# Arduino-DIP.net
KiCad netlist of a schematic drawn in EAGLE
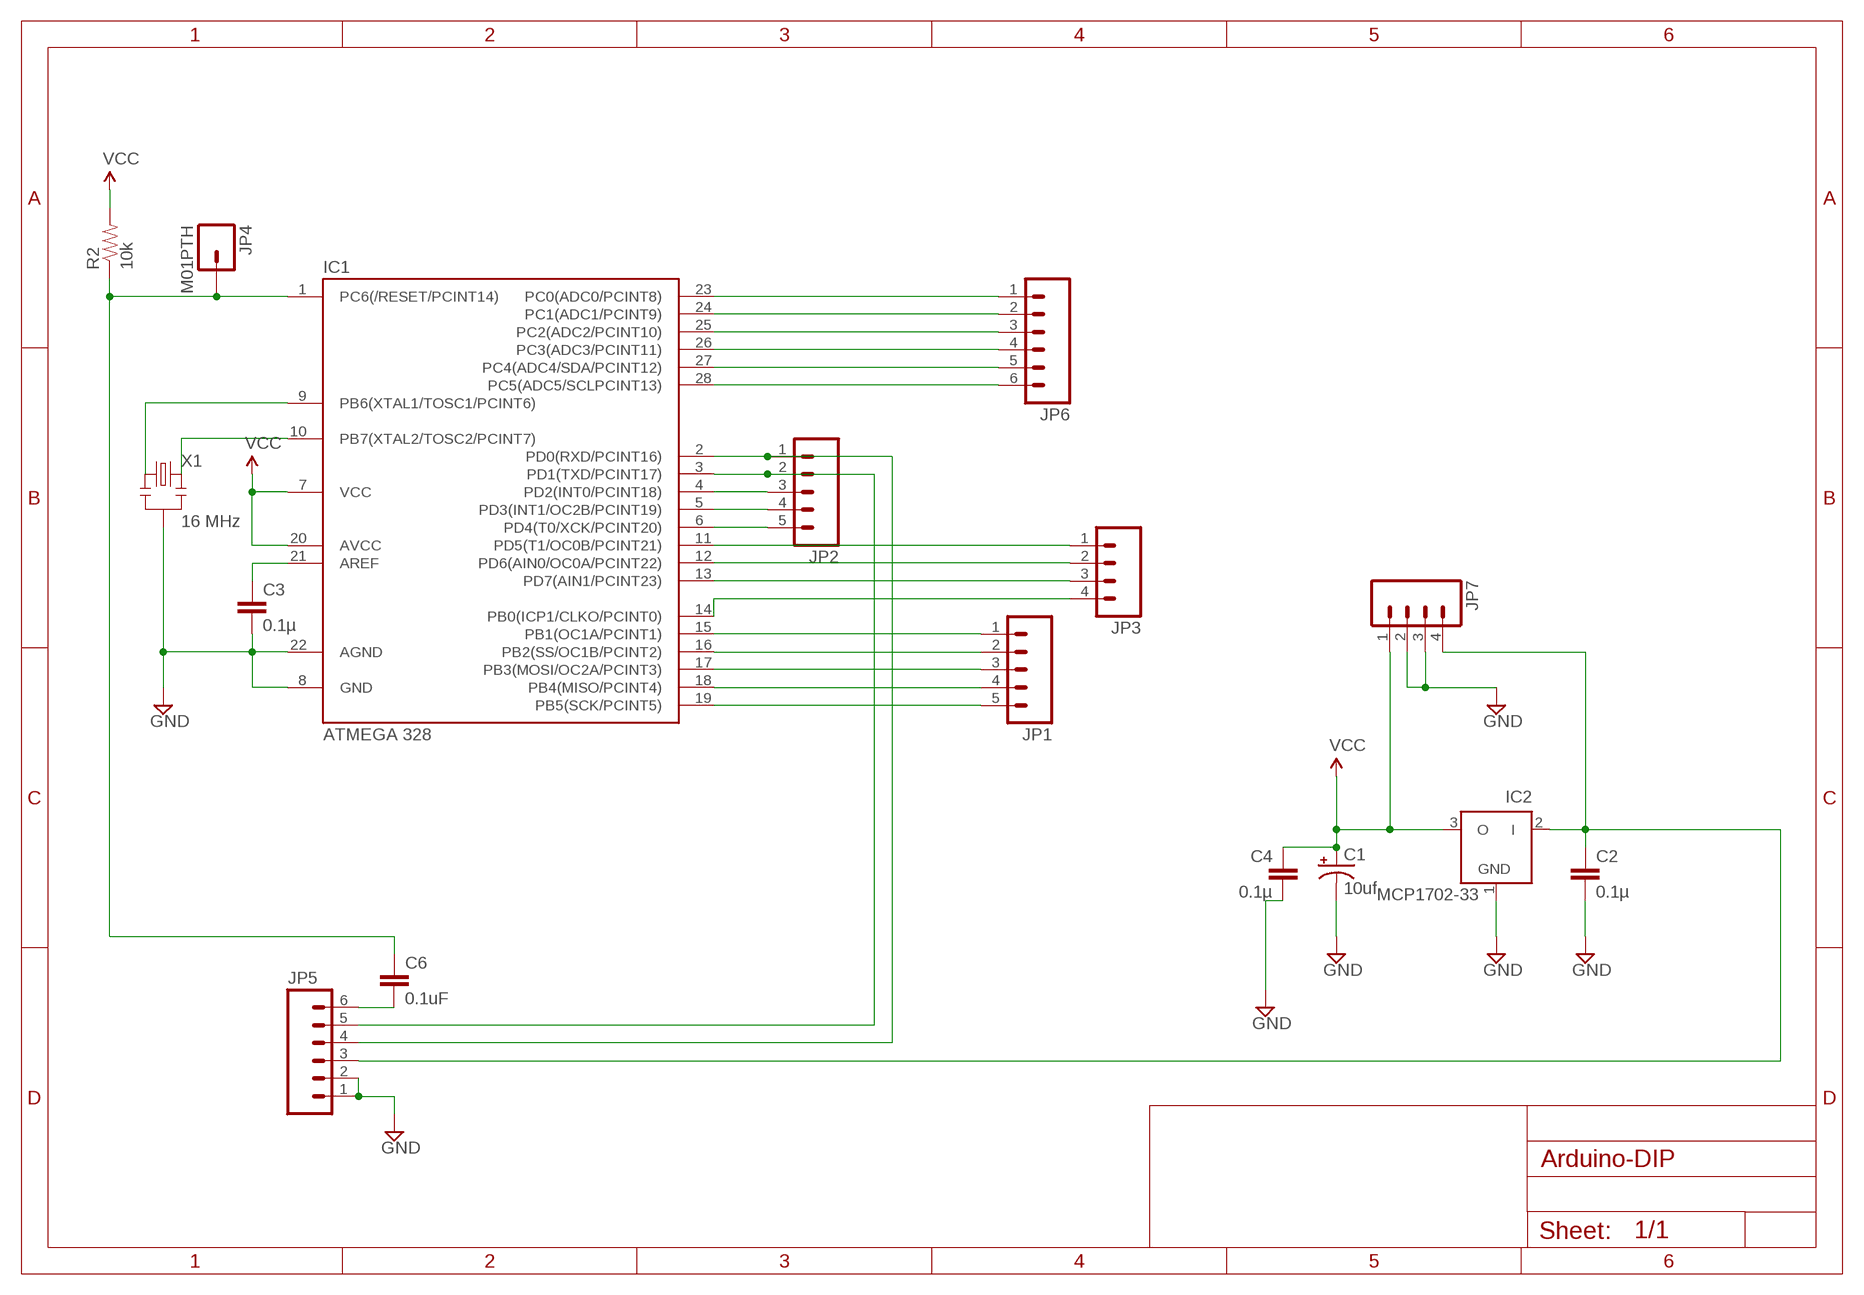
[diagram p0: schematic, sheet 1]

(export (version "E")
  (design (tool "Eeschema 10.0.6"))
  (components
    (comp (ref "C1")
      (value "10uf")
      (footprint "eagle-import:CPOL-RADIAL-10UF-25V")
      (libsource (lib "eagle-import") (part "CAP_POLPTH2"))
    )
    (comp (ref "C2")
      (value "0.1µ")
      (footprint "eagle-import:C025-024X044")
      (libsource (lib "eagle-import") (part "C-EU025-024X044"))
    )
    (comp (ref "C3")
      (value "0.1µ")
      (footprint "eagle-import:C025-024X044")
      (libsource (lib "eagle-import") (part "C-EU025-024X044"))
    )
    (comp (ref "C4")
      (value "0.1µ")
      (footprint "eagle-import:C025-024X044")
      (libsource (lib "eagle-import") (part "C-EU025-024X044"))
    )
    (comp (ref "C6")
      (value "0.1uF")
      (footprint "eagle-import:CAP-PTH-5MM")
      (libsource (lib "eagle-import") (part "CAPPTH1"))
    )
    (comp (ref "IC1")
      (value "ATMEGA 328")
      (footprint "eagle-import:DIL28-3")
      (libsource (lib "eagle-import") (part "ATMEGA48/88/168-PU"))
    )
    (comp (ref "IC2")
      (value "MCP1702-33")
      (footprint "eagle-import:TO92")
      (libsource (lib "eagle-import") (part "MCP1702Z"))
    )
    (comp (ref "JP1")
      (value "M05PTH")
      (footprint "eagle-import:1X05")
      (libsource (lib "eagle-import") (part "M05PTH"))
    )
    (comp (ref "JP2")
      (value "M05PTH")
      (footprint "eagle-import:1X05")
      (libsource (lib "eagle-import") (part "M05PTH"))
    )
    (comp (ref "JP3")
      (value "M04PTH")
      (footprint "eagle-import:1X04")
      (libsource (lib "eagle-import") (part "M04PTH"))
    )
    (comp (ref "JP4")
      (value "M01PTH")
      (footprint "eagle-import:1X01")
      (libsource (lib "eagle-import") (part "M01PTH"))
    )
    (comp (ref "JP5")
      (value "M06NO_SILK")
      (footprint "eagle-import:1X06_NO_SILK")
      (libsource (lib "eagle-import") (part "M06NO_SILK"))
    )
    (comp (ref "JP6")
      (value "M06NO_SILK")
      (footprint "eagle-import:1X06_NO_SILK")
      (libsource (lib "eagle-import") (part "M06NO_SILK"))
    )
    (comp (ref "JP7")
      (value "M04PTH")
      (footprint "eagle-import:1X04")
      (libsource (lib "eagle-import") (part "M04PTH"))
    )
    (comp (ref "R2")
      (value "10k")
      (footprint "eagle-import:1_6W-RES")
      (libsource (lib "eagle-import") (part "RESISTORPTH-1/6W"))
    )
    (comp (ref "X1")
      (value "16 MHz")
      (footprint "eagle-import:RESONATOR-PTH")
      (libsource (lib "eagle-import") (part "RESONATORPTH"))
    )
  )
  (nets
    (net (code "1") (name "GND") (class "Default")
      (node (ref "C1") (pin "2") (pinfunction "-_2") (pintype "passive"))
      (node (ref "C2") (pin "2") (pinfunction "2_2") (pintype "passive"))
      (node (ref "C3") (pin "2") (pinfunction "2_2") (pintype "passive"))
      (node (ref "C4") (pin "2") (pinfunction "2_2") (pintype "passive"))
      (node (ref "IC1") (pin "22") (pinfunction "AGND_22") (pintype "power_in"))
      (node (ref "IC1") (pin "8") (pinfunction "GND_8") (pintype "power_in"))
      (node (ref "IC2") (pin "1") (pinfunction "GND_1") (pintype "power_in"))
      (node (ref "JP5") (pin "1") (pinfunction "1_1") (pintype "passive"))
      (node (ref "JP5") (pin "2") (pinfunction "2_2") (pintype "passive"))
      (node (ref "JP7") (pin "2") (pinfunction "2_2") (pintype "passive"))
      (node (ref "JP7") (pin "3") (pinfunction "3_3") (pintype "passive"))
      (node (ref "X1") (pin "2") (pinfunction "2_2") (pintype "passive"))
    )
    (net (code "2") (name "Net-(C6-Pad2)") (class "Default")
      (node (ref "C6") (pin "2") (pinfunction "2_2") (pintype "passive"))
      (node (ref "JP5") (pin "6") (pinfunction "6_6") (pintype "passive"))
    )
    (net (code "3") (name "Net-(IC1-AREF)") (class "Default")
      (node (ref "C3") (pin "1") (pinfunction "1_1") (pintype "passive"))
      (node (ref "IC1") (pin "21") (pinfunction "AREF_21") (pintype "passive"))
    )
    (net (code "4") (name "Net-(IC1-PB0(ICP1{slash}CLKO{slash}PCINT0))") (class "Default")
      (node (ref "IC1") (pin "14") (pinfunction "PB0(ICP1/CLKO/PCINT0)_14") (pintype "bidirectional"))
      (node (ref "JP3") (pin "4") (pinfunction "4_4") (pintype "passive"))
    )
    (net (code "5") (name "Net-(IC1-PB1(OC1A{slash}PCINT1))") (class "Default")
      (node (ref "IC1") (pin "15") (pinfunction "PB1(OC1A/PCINT1)_15") (pintype "bidirectional"))
      (node (ref "JP1") (pin "1") (pinfunction "1_1") (pintype "passive"))
    )
    (net (code "6") (name "Net-(IC1-PB2(SS{slash}OC1B{slash}PCINT2))") (class "Default")
      (node (ref "IC1") (pin "16") (pinfunction "PB2(SS/OC1B/PCINT2)_16") (pintype "bidirectional"))
      (node (ref "JP1") (pin "2") (pinfunction "2_2") (pintype "passive"))
    )
    (net (code "7") (name "Net-(IC1-PB3(MOSI{slash}OC2A{slash}PCINT3))") (class "Default")
      (node (ref "IC1") (pin "17") (pinfunction "PB3(MOSI/OC2A/PCINT3)_17") (pintype "bidirectional"))
      (node (ref "JP1") (pin "3") (pinfunction "3_3") (pintype "passive"))
    )
    (net (code "8") (name "Net-(IC1-PB4(MISO{slash}PCINT4))") (class "Default")
      (node (ref "IC1") (pin "18") (pinfunction "PB4(MISO/PCINT4)_18") (pintype "bidirectional"))
      (node (ref "JP1") (pin "4") (pinfunction "4_4") (pintype "passive"))
    )
    (net (code "9") (name "Net-(IC1-PB5(SCK{slash}PCINT5))") (class "Default")
      (node (ref "IC1") (pin "19") (pinfunction "PB5(SCK/PCINT5)_19") (pintype "bidirectional"))
      (node (ref "JP1") (pin "5") (pinfunction "5_5") (pintype "passive"))
    )
    (net (code "10") (name "Net-(IC1-PB6(XTAL1{slash}TOSC1{slash}PCINT6))") (class "Default")
      (node (ref "IC1") (pin "9") (pinfunction "PB6(XTAL1/TOSC1/PCINT6)_9") (pintype "bidirectional"))
      (node (ref "X1") (pin "1") (pinfunction "1_1") (pintype "passive"))
    )
    (net (code "11") (name "Net-(IC1-PB7(XTAL2{slash}TOSC2{slash}PCINT7))") (class "Default")
      (node (ref "IC1") (pin "10") (pinfunction "PB7(XTAL2/TOSC2/PCINT7)_10") (pintype "bidirectional"))
      (node (ref "X1") (pin "3") (pinfunction "3_3") (pintype "passive"))
    )
    (net (code "12") (name "Net-(IC1-PC0(ADC0{slash}PCINT8))") (class "Default")
      (node (ref "IC1") (pin "23") (pinfunction "PC0(ADC0/PCINT8)_23") (pintype "bidirectional"))
      (node (ref "JP6") (pin "1") (pinfunction "1_1") (pintype "passive"))
    )
    (net (code "13") (name "Net-(IC1-PC1(ADC1{slash}PCINT9))") (class "Default")
      (node (ref "IC1") (pin "24") (pinfunction "PC1(ADC1/PCINT9)_24") (pintype "bidirectional"))
      (node (ref "JP6") (pin "2") (pinfunction "2_2") (pintype "passive"))
    )
    (net (code "14") (name "Net-(IC1-PC2(ADC2{slash}PCINT10))") (class "Default")
      (node (ref "IC1") (pin "25") (pinfunction "PC2(ADC2/PCINT10)_25") (pintype "bidirectional"))
      (node (ref "JP6") (pin "3") (pinfunction "3_3") (pintype "passive"))
    )
    (net (code "15") (name "Net-(IC1-PC3(ADC3{slash}PCINT11))") (class "Default")
      (node (ref "IC1") (pin "26") (pinfunction "PC3(ADC3/PCINT11)_26") (pintype "bidirectional"))
      (node (ref "JP6") (pin "4") (pinfunction "4_4") (pintype "passive"))
    )
    (net (code "16") (name "Net-(IC1-PC4(ADC4{slash}SDA{slash}PCINT12))") (class "Default")
      (node (ref "IC1") (pin "27") (pinfunction "PC4(ADC4/SDA/PCINT12)_27") (pintype "bidirectional"))
      (node (ref "JP6") (pin "5") (pinfunction "5_5") (pintype "passive"))
    )
    (net (code "17") (name "Net-(IC1-PC5(ADC5{slash}SCLPCINT13))") (class "Default")
      (node (ref "IC1") (pin "28") (pinfunction "PC5(ADC5/SCLPCINT13)_28") (pintype "bidirectional"))
      (node (ref "JP6") (pin "6") (pinfunction "6_6") (pintype "passive"))
    )
    (net (code "18") (name "Net-(IC1-PC6({slash}RESET{slash}PCINT14))") (class "Default")
      (node (ref "C6") (pin "1") (pinfunction "1_1") (pintype "passive"))
      (node (ref "IC1") (pin "1") (pinfunction "PC6(/RESET/PCINT14)_1") (pintype "bidirectional"))
      (node (ref "JP4") (pin "1") (pinfunction "1_1") (pintype "passive"))
      (node (ref "R2") (pin "1") (pinfunction "1_1") (pintype "passive"))
    )
    (net (code "19") (name "Net-(IC1-PD0(RXD{slash}PCINT16))") (class "Default")
      (node (ref "IC1") (pin "2") (pinfunction "PD0(RXD/PCINT16)_2") (pintype "bidirectional"))
      (node (ref "JP2") (pin "1") (pinfunction "1_1") (pintype "passive"))
      (node (ref "JP5") (pin "4") (pinfunction "4_4") (pintype "passive"))
    )
    (net (code "20") (name "Net-(IC1-PD1(TXD{slash}PCINT17))") (class "Default")
      (node (ref "IC1") (pin "3") (pinfunction "PD1(TXD/PCINT17)_3") (pintype "bidirectional"))
      (node (ref "JP2") (pin "2") (pinfunction "2_2") (pintype "passive"))
      (node (ref "JP5") (pin "5") (pinfunction "5_5") (pintype "passive"))
    )
    (net (code "21") (name "Net-(IC1-PD2(INT0{slash}PCINT18))") (class "Default")
      (node (ref "IC1") (pin "4") (pinfunction "PD2(INT0/PCINT18)_4") (pintype "bidirectional"))
      (node (ref "JP2") (pin "3") (pinfunction "3_3") (pintype "passive"))
    )
    (net (code "22") (name "Net-(IC1-PD3(INT1{slash}OC2B{slash}PCINT19))") (class "Default")
      (node (ref "IC1") (pin "5") (pinfunction "PD3(INT1/OC2B/PCINT19)_5") (pintype "bidirectional"))
      (node (ref "JP2") (pin "4") (pinfunction "4_4") (pintype "passive"))
    )
    (net (code "23") (name "Net-(IC1-PD4(T0{slash}XCK{slash}PCINT20))") (class "Default")
      (node (ref "IC1") (pin "6") (pinfunction "PD4(T0/XCK/PCINT20)_6") (pintype "bidirectional"))
      (node (ref "JP2") (pin "5") (pinfunction "5_5") (pintype "passive"))
    )
    (net (code "24") (name "Net-(IC1-PD5(T1{slash}OC0B{slash}PCINT21))") (class "Default")
      (node (ref "IC1") (pin "11") (pinfunction "PD5(T1/OC0B/PCINT21)_11") (pintype "bidirectional"))
      (node (ref "JP3") (pin "1") (pinfunction "1_1") (pintype "passive"))
    )
    (net (code "25") (name "Net-(IC1-PD6(AIN0{slash}OC0A{slash}PCINT22))") (class "Default")
      (node (ref "IC1") (pin "12") (pinfunction "PD6(AIN0/OC0A/PCINT22)_12") (pintype "bidirectional"))
      (node (ref "JP3") (pin "2") (pinfunction "2_2") (pintype "passive"))
    )
    (net (code "26") (name "Net-(IC1-PD7(AIN1{slash}PCINT23))") (class "Default")
      (node (ref "IC1") (pin "13") (pinfunction "PD7(AIN1/PCINT23)_13") (pintype "bidirectional"))
      (node (ref "JP3") (pin "3") (pinfunction "3_3") (pintype "passive"))
    )
    (net (code "27") (name "Net-(IC2-I)") (class "Default")
      (node (ref "C2") (pin "1") (pinfunction "1_1") (pintype "passive"))
      (node (ref "IC2") (pin "2") (pinfunction "I_2") (pintype "input"))
      (node (ref "JP5") (pin "3") (pinfunction "3_3") (pintype "passive"))
      (node (ref "JP7") (pin "4") (pinfunction "4_4") (pintype "passive"))
    )
    (net (code "28") (name "VCC") (class "Default")
      (node (ref "C1") (pin "1") (pinfunction "+_1") (pintype "passive"))
      (node (ref "C4") (pin "1") (pinfunction "1_1") (pintype "passive"))
      (node (ref "IC1") (pin "20") (pinfunction "AVCC_20") (pintype "passive"))
      (node (ref "IC1") (pin "7") (pinfunction "VCC_7") (pintype "power_in"))
      (node (ref "IC2") (pin "3") (pinfunction "O_3") (pintype "input"))
      (node (ref "JP7") (pin "1") (pinfunction "1_1") (pintype "passive"))
      (node (ref "R2") (pin "2") (pinfunction "2_2") (pintype "passive"))
    )
  )
)
